# R2D.net
KiCad netlist of a schematic drawn in Altium Designer
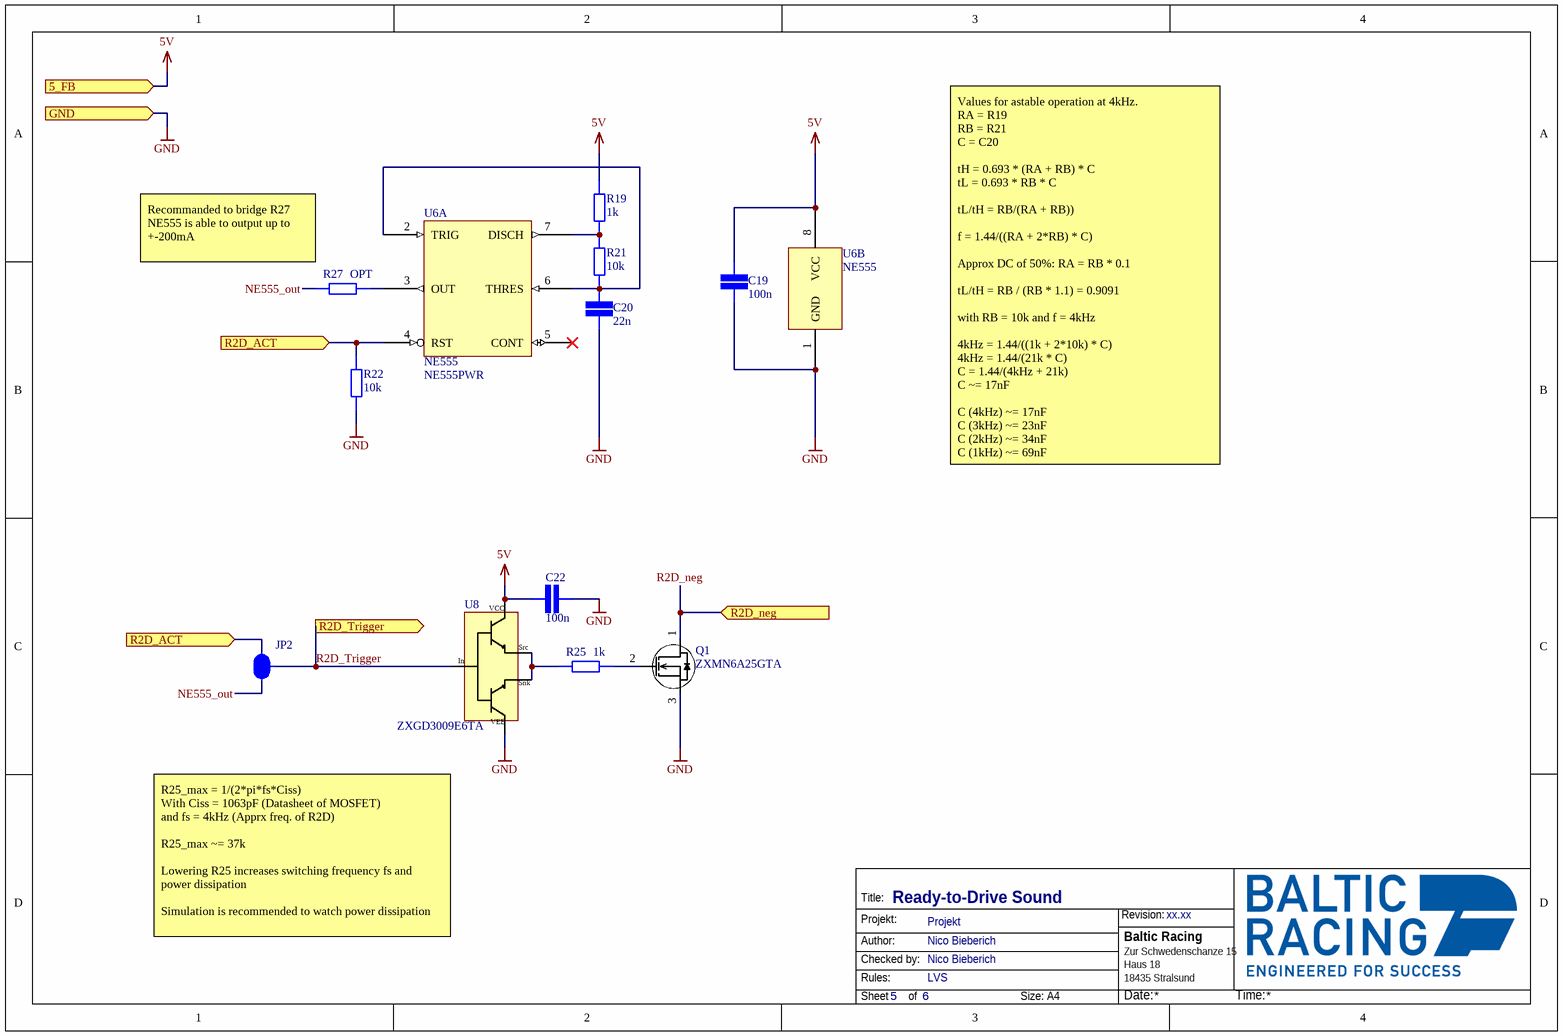
[diagram p0: R2D.SchDoc]

(export (version "E")
  (design (tool "Eeschema 10.0.6"))
  (components
    (comp (ref "C19")
      (value "100n")
      (footprint "CAP 0603/1608")
      (description "Capacitor with multiple Footprints")
      (fields (field (name "VOLTAGE") "16") (field (name "Comment") "SMD Capacitor"))
      (libsource (lib "Standardbauteile") (part "SMD Capacitor"))
    )
    (comp (ref "C20")
      (value "22n")
      (footprint "CAP 0603/1608")
      (description "Capacitor with multiple Footprints")
      (fields (field (name "VOLTAGE") "16") (field (name "Comment") "SMD Capacitor"))
      (libsource (lib "Standardbauteile") (part "SMD Capacitor"))
    )
    (comp (ref "C22")
      (value "100n")
      (footprint "CAP 0603/1608")
      (description "Capacitor with multiple Footprints")
      (fields (field (name "VOLTAGE") "16") (field (name "Comment") "SMD Capacitor"))
      (libsource (lib "") (part "SMD Capacitor_1"))
    )
    (comp (ref "JP2")
      (value "JUMPERID")
      (footprint "SMD-JUMPER-3")
      (libsource (lib "Standardbauteile") (part "SMD Jumper 3"))
    )
    (comp (ref "Q1")
      (value "ZXMN6A25GTA")
      (footprint "ZXMN6A25GTA")
      (description "Diodes Inc. ZXMN6A25GTA\r\nN-Channel MOSFET, 60V, 6.7A")
      (libsource (lib "libNico") (part "ZXMN6A25GTA"))
    )
    (comp (ref "R19")
      (value "1k")
      (footprint "STACKPOLE CSR0603")
      (description "Resistor with multiple footprints")
      (fields (field (name "POWER") "0.1W") (field (name "Comment") "SMD Resistor"))
      (libsource (lib "Standardbauteile") (part "SMD Resistor"))
    )
    (comp (ref "R21")
      (value "10k")
      (footprint "STACKPOLE CSR0603")
      (description "Resistor with multiple footprints")
      (fields (field (name "POWER") "0.1W") (field (name "Comment") "SMD Resistor"))
      (libsource (lib "Standardbauteile") (part "SMD Resistor"))
    )
    (comp (ref "R22")
      (value "10k")
      (footprint "STACKPOLE CSR0603")
      (description "Resistor with multiple footprints")
      (fields (field (name "POWER") "0.1W") (field (name "Comment") "SMD Resistor"))
      (libsource (lib "Standardbauteile") (part "SMD Resistor"))
    )
    (comp (ref "R25")
      (value "1k")
      (footprint "STACKPOLE CSR0603")
      (description "Resistor with multiple footprints")
      (fields (field (name "POWER") "0.1W") (field (name "Comment") "SMD Resistor"))
      (libsource (lib "Standardbauteile") (part "SMD Resistor"))
    )
    (comp (ref "R27")
      (value "OPT")
      (footprint "STACKPOLE CSR0603")
      (description "Resistor with multiple footprints")
      (fields (field (name "POWER") "0.1W") (field (name "Comment") "SMD Resistor"))
      (libsource (lib "Standardbauteile") (part "SMD Resistor"))
    )
    (comp (ref "U6")
      (value "NE555")
      (footprint "NE555PWR")
      (description "Single Precision Timer")
      (fields (field (name "ALTIUM_VALUE") "NE555PWR"))
      (libsource (lib "libNico") (part "NE555"))
    )
    (comp (ref "U8")
      (value "ZXGD3009E6TA")
      (footprint "ZXGD3009E6TA")
      (description "Diodes Inc. ZXGD3009E6TA\r\nMOSFET Gate Driver, 1Ch, 1A")
      (libsource (lib "libNico") (part "ZXGD3009E6TA"))
    )
  )
  (nets
    (net (code "1") (name "/NE555_out") (class "Default")
      (node (ref "JP2") (pin "3") (pinfunction "3_3") (pintype "passive"))
      (node (ref "R27") (pin "2") (pinfunction "2_2") (pintype "passive"))
    )
    (net (code "2") (name "/R2D_ACT") (class "Default")
      (node (ref "JP2") (pin "1") (pinfunction "1_1") (pintype "passive"))
      (node (ref "R22") (pin "2") (pinfunction "2_2") (pintype "passive"))
      (node (ref "U6") (pin "4") (pinfunction "RST_4") (pintype "input"))
    )
    (net (code "3") (name "/R2D_Trigger") (class "Default")
      (node (ref "JP2") (pin "2") (pinfunction "2_2") (pintype "passive"))
      (node (ref "U8") (pin "2") (pinfunction "In_2") (pintype "passive"))
    )
    (net (code "4") (name "/R2D_neg") (class "Default")
      (node (ref "Q1") (pin "1") (pinfunction "D_1") (pintype "passive"))
    )
    (net (code "5") (name "5V") (class "Default")
      (node (ref "C19") (pin "2") (pinfunction "2_2") (pintype "passive"))
      (node (ref "C22") (pin "1") (pinfunction "1_1") (pintype "passive"))
      (node (ref "R19") (pin "2") (pinfunction "2_2") (pintype "passive"))
      (node (ref "U6") (pin "8") (pinfunction "VCC_8") (pintype "passive"))
      (node (ref "U8") (pin "1") (pinfunction "VCC_1") (pintype "passive"))
    )
    (net (code "6") (name "GND") (class "Default")
      (node (ref "C19") (pin "1") (pinfunction "1_1") (pintype "passive"))
      (node (ref "C20") (pin "1") (pinfunction "1_1") (pintype "passive"))
      (node (ref "C22") (pin "2") (pinfunction "2_2") (pintype "passive"))
      (node (ref "Q1") (pin "3") (pinfunction "S_3") (pintype "passive"))
      (node (ref "R22") (pin "1") (pinfunction "1_1") (pintype "passive"))
      (node (ref "U6") (pin "1") (pinfunction "GND_1") (pintype "passive"))
      (node (ref "U8") (pin "3") (pinfunction "VEE_3") (pintype "passive"))
    )
    (net (code "7") (name "Net-(Q1-G)") (class "Default")
      (node (ref "Q1") (pin "2") (pinfunction "G_2") (pintype "passive"))
      (node (ref "R25") (pin "1") (pinfunction "1_1") (pintype "passive"))
    )
    (net (code "8") (name "Net-(U6A-DISCH)") (class "Default")
      (node (ref "R19") (pin "1") (pinfunction "1_1") (pintype "passive"))
      (node (ref "R21") (pin "2") (pinfunction "2_2") (pintype "passive"))
      (node (ref "U6") (pin "7") (pinfunction "DISCH_7") (pintype "output"))
    )
    (net (code "9") (name "Net-(U6A-OUT)") (class "Default")
      (node (ref "R27") (pin "1") (pinfunction "1_1") (pintype "passive"))
      (node (ref "U6") (pin "3") (pinfunction "OUT_3") (pintype "output"))
    )
    (net (code "10") (name "Net-(U6A-THRES)") (class "Default")
      (node (ref "C20") (pin "2") (pinfunction "2_2") (pintype "passive"))
      (node (ref "R21") (pin "1") (pinfunction "1_1") (pintype "passive"))
      (node (ref "U6") (pin "2") (pinfunction "TRIG_2") (pintype "input"))
      (node (ref "U6") (pin "6") (pinfunction "THRES_6") (pintype "input"))
    )
    (net (code "11") (name "Net-(U8-Snk)") (class "Default")
      (node (ref "R25") (pin "2") (pinfunction "2_2") (pintype "passive"))
      (node (ref "U8") (pin "4") (pinfunction "Snk_4") (pintype "passive"))
      (node (ref "U8") (pin "6") (pinfunction "Src_6") (pintype "passive"))
    )
    (net (code "12") (name "unconnected-(U6A-CONT-Pad5)") (class "Default")
      (node (ref "U6") (pin "5") (pinfunction "CONT_5") (pintype "bidirectional+no_connect"))
    )
  )
)
